# ESB32CARRIER.net
KiCad netlist of a schematic drawn in EAGLE
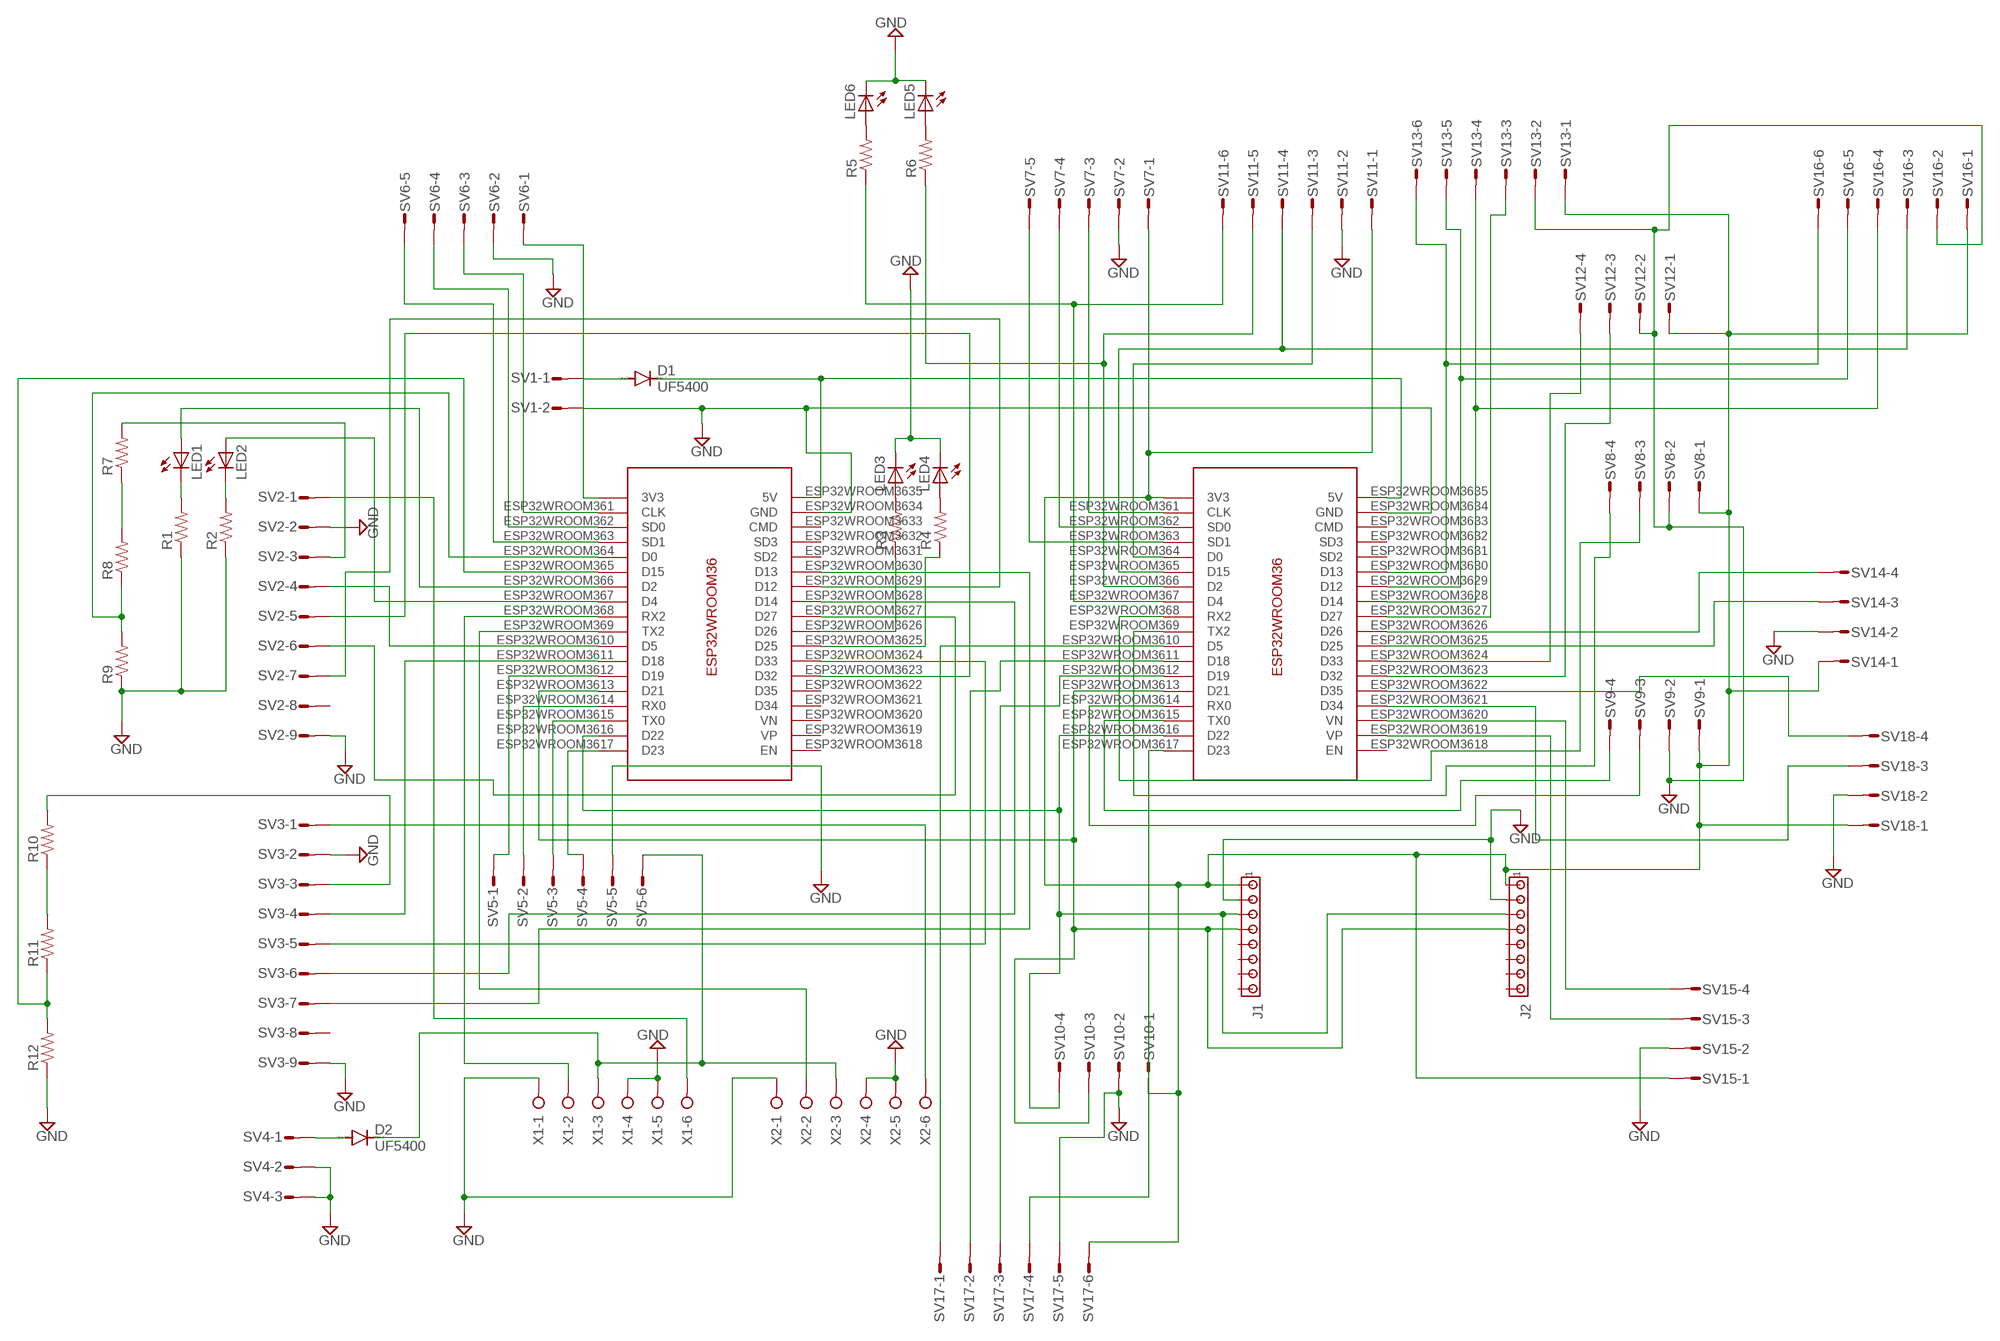
[diagram p0: schematic, sheet 1]

(export (version "E")
  (design (tool "Eeschema 10.0.6"))
  (components
    (comp (ref "D1")
      (value "UF5400")
      (footprint "eagle-import:DO201-15")
      (libsource (lib "eagle-import") (part "UF5400"))
    )
    (comp (ref "D2")
      (value "UF5400")
      (footprint "eagle-import:DO201-15")
      (libsource (lib "eagle-import") (part "UF5400"))
    )
    (comp (ref "J1")
      (value "MTA08-100")
      (footprint "eagle-import:10X08MTA")
      (libsource (lib "eagle-import") (part "MTA08-100"))
    )
    (comp (ref "J2")
      (value "MTA08-100")
      (footprint "eagle-import:10X08MTA")
      (libsource (lib "eagle-import") (part "MTA08-100"))
    )
    (comp (ref "LED1")
      (value "LED3MM")
      (footprint "eagle-import:LED3MM")
      (libsource (lib "eagle-import") (part "LED3MM"))
    )
    (comp (ref "LED2")
      (value "LED3MM")
      (footprint "eagle-import:LED3MM")
      (libsource (lib "eagle-import") (part "LED3MM"))
    )
    (comp (ref "LED3")
      (value "LED3MM")
      (footprint "eagle-import:LED3MM")
      (libsource (lib "eagle-import") (part "LED3MM"))
    )
    (comp (ref "LED4")
      (value "LED3MM")
      (footprint "eagle-import:LED3MM")
      (libsource (lib "eagle-import") (part "LED3MM"))
    )
    (comp (ref "LED5")
      (value "LED3MM")
      (footprint "eagle-import:LED3MM")
      (libsource (lib "eagle-import") (part "LED3MM"))
    )
    (comp (ref "LED6")
      (value "LED3MM")
      (footprint "eagle-import:LED3MM")
      (libsource (lib "eagle-import") (part "LED3MM"))
    )
    (comp (ref "R1")
      (value "R-US_0207/10")
      (footprint "eagle-import:0207_10")
      (libsource (lib "eagle-import") (part "R-US_0207/10"))
    )
    (comp (ref "R2")
      (value "R-US_0207/10")
      (footprint "eagle-import:0207_10")
      (libsource (lib "eagle-import") (part "R-US_0207/10"))
    )
    (comp (ref "R3")
      (value "R-US_0207/10")
      (footprint "eagle-import:0207_10")
      (libsource (lib "eagle-import") (part "R-US_0207/10"))
    )
    (comp (ref "R4")
      (value "R-US_0207/10")
      (footprint "eagle-import:0207_10")
      (libsource (lib "eagle-import") (part "R-US_0207/10"))
    )
    (comp (ref "R5")
      (value "R-US_0207/10")
      (footprint "eagle-import:0207_10")
      (libsource (lib "eagle-import") (part "R-US_0207/10"))
    )
    (comp (ref "R6")
      (value "R-US_0207/10")
      (footprint "eagle-import:0207_10")
      (libsource (lib "eagle-import") (part "R-US_0207/10"))
    )
    (comp (ref "R7")
      (value "R-US_0207/10")
      (footprint "eagle-import:0207_10")
      (libsource (lib "eagle-import") (part "R-US_0207/10"))
    )
    (comp (ref "R8")
      (value "R-US_0207/10")
      (footprint "eagle-import:0207_10")
      (libsource (lib "eagle-import") (part "R-US_0207/10"))
    )
    (comp (ref "R9")
      (value "R-US_0207/10")
      (footprint "eagle-import:0207_10")
      (libsource (lib "eagle-import") (part "R-US_0207/10"))
    )
    (comp (ref "R10")
      (value "R-US_0207/10")
      (footprint "eagle-import:0207_10")
      (libsource (lib "eagle-import") (part "R-US_0207/10"))
    )
    (comp (ref "R11")
      (value "R-US_0207/10")
      (footprint "eagle-import:0207_10")
      (libsource (lib "eagle-import") (part "R-US_0207/10"))
    )
    (comp (ref "R12")
      (value "R-US_0207/10")
      (footprint "eagle-import:0207_10")
      (libsource (lib "eagle-import") (part "R-US_0207/10"))
    )
    (comp (ref "SV1")
      (value "L02P")
      (footprint "eagle-import:L02P")
      (libsource (lib "eagle-import") (part "L02P"))
    )
    (comp (ref "SV2")
      (value "L09P")
      (footprint "eagle-import:L09P")
      (libsource (lib "eagle-import") (part "L09P"))
    )
    (comp (ref "SV3")
      (value "L09P")
      (footprint "eagle-import:L09P")
      (libsource (lib "eagle-import") (part "L09P"))
    )
    (comp (ref "SV4")
      (value "L03P")
      (footprint "eagle-import:L03P")
      (libsource (lib "eagle-import") (part "L03P"))
    )
    (comp (ref "SV5")
      (value "L06P")
      (footprint "eagle-import:L06P")
      (libsource (lib "eagle-import") (part "L06P"))
    )
    (comp (ref "SV6")
      (value "L05P")
      (footprint "eagle-import:L05P")
      (libsource (lib "eagle-import") (part "L05P"))
    )
    (comp (ref "SV7")
      (value "L05P")
      (footprint "eagle-import:L05P")
      (libsource (lib "eagle-import") (part "L05P"))
    )
    (comp (ref "SV8")
      (value "L04P")
      (footprint "eagle-import:L04P")
      (libsource (lib "eagle-import") (part "L04P"))
    )
    (comp (ref "SV9")
      (value "L04P")
      (footprint "eagle-import:L04P")
      (libsource (lib "eagle-import") (part "L04P"))
    )
    (comp (ref "SV10")
      (value "L04P")
      (footprint "eagle-import:L04P")
      (libsource (lib "eagle-import") (part "L04P"))
    )
    (comp (ref "SV11")
      (value "L06P")
      (footprint "eagle-import:L06P")
      (libsource (lib "eagle-import") (part "L06P"))
    )
    (comp (ref "SV12")
      (value "L04P")
      (footprint "eagle-import:L04P")
      (libsource (lib "eagle-import") (part "L04P"))
    )
    (comp (ref "SV13")
      (value "L06P")
      (footprint "eagle-import:L06P")
      (libsource (lib "eagle-import") (part "L06P"))
    )
    (comp (ref "SV14")
      (value "L04P")
      (footprint "eagle-import:L04P")
      (libsource (lib "eagle-import") (part "L04P"))
    )
    (comp (ref "SV15")
      (value "L04P")
      (footprint "eagle-import:L04P")
      (libsource (lib "eagle-import") (part "L04P"))
    )
    (comp (ref "SV16")
      (value "L06P")
      (footprint "eagle-import:L06P")
      (libsource (lib "eagle-import") (part "L06P"))
    )
    (comp (ref "SV17")
      (value "L06P")
      (footprint "eagle-import:L06P")
      (libsource (lib "eagle-import") (part "L06P"))
    )
    (comp (ref "SV18")
      (value "L04P")
      (footprint "eagle-import:L04P")
      (libsource (lib "eagle-import") (part "L04P"))
    )
    (comp (ref "U$1")
      (value "ESP32WROOM36")
      (footprint "eagle-import:ESP32WROOM36PINDIP")
      (libsource (lib "eagle-import") (part "ESP32WROOM36"))
    )
    (comp (ref "U$2")
      (value "ESP32WROOM36")
      (footprint "eagle-import:ESP32WROOM36PINDIP")
      (libsource (lib "eagle-import") (part "ESP32WROOM36"))
    )
    (comp (ref "X1")
      (value "W237-06P")
      (footprint "eagle-import:W237-6P")
      (libsource (lib "eagle-import") (part "W237-06P"))
    )
    (comp (ref "X2")
      (value "W237-06P")
      (footprint "eagle-import:W237-6P")
      (libsource (lib "eagle-import") (part "W237-06P"))
    )
  )
  (nets
    (net (code "1") (name "GND") (class "Default")
      (node (ref "J1") (pin "2") (pinfunction "2_2") (pintype "passive"))
      (node (ref "J2") (pin "2") (pinfunction "2_2") (pintype "passive"))
      (node (ref "LED3") (pin "K") (pinfunction "C_K") (pintype "passive"))
      (node (ref "LED4") (pin "K") (pinfunction "C_K") (pintype "passive"))
      (node (ref "LED5") (pin "K") (pinfunction "C_K") (pintype "passive"))
      (node (ref "LED6") (pin "K") (pinfunction "C_K") (pintype "passive"))
      (node (ref "R1") (pin "1") (pinfunction "1_1") (pintype "passive"))
      (node (ref "R12") (pin "1") (pinfunction "1_1") (pintype "passive"))
      (node (ref "R2") (pin "1") (pinfunction "1_1") (pintype "passive"))
      (node (ref "R9") (pin "1") (pinfunction "1_1") (pintype "passive"))
      (node (ref "SV1") (pin "2") (pinfunction "S_2") (pintype "passive"))
      (node (ref "SV10") (pin "2") (pinfunction "S_2") (pintype "passive"))
      (node (ref "SV11") (pin "2") (pinfunction "S_2") (pintype "passive"))
      (node (ref "SV12") (pin "2") (pinfunction "S_2") (pintype "passive"))
      (node (ref "SV13") (pin "2") (pinfunction "S_2") (pintype "passive"))
      (node (ref "SV14") (pin "2") (pinfunction "S_2") (pintype "passive"))
      (node (ref "SV15") (pin "2") (pinfunction "S_2") (pintype "passive"))
      (node (ref "SV16") (pin "2") (pinfunction "S_2") (pintype "passive"))
      (node (ref "SV17") (pin "5") (pinfunction "S_5") (pintype "passive"))
      (node (ref "SV18") (pin "2") (pinfunction "S_2") (pintype "passive"))
      (node (ref "SV2") (pin "2") (pinfunction "S_2") (pintype "passive"))
      (node (ref "SV2") (pin "9") (pinfunction "S_9") (pintype "passive"))
      (node (ref "SV3") (pin "2") (pinfunction "S_2") (pintype "passive"))
      (node (ref "SV3") (pin "9") (pinfunction "S_9") (pintype "passive"))
      (node (ref "SV4") (pin "2") (pinfunction "S_2") (pintype "passive"))
      (node (ref "SV4") (pin "3") (pinfunction "S_3") (pintype "passive"))
      (node (ref "SV5") (pin "5") (pinfunction "S_5") (pintype "passive"))
      (node (ref "SV6") (pin "2") (pinfunction "S_2") (pintype "passive"))
      (node (ref "SV7") (pin "2") (pinfunction "S_2") (pintype "passive"))
      (node (ref "SV8") (pin "2") (pinfunction "S_2") (pintype "passive"))
      (node (ref "SV9") (pin "2") (pinfunction "S_2") (pintype "passive"))
      (node (ref "U$1") (pin "ESP32WROOM3634") (pinfunction "GND_ESP32WROOM3634") (pintype "bidirectional"))
      (node (ref "U$2") (pin "ESP32WROOM3634") (pinfunction "GND_ESP32WROOM3634") (pintype "bidirectional"))
      (node (ref "X1") (pin "1") (pinfunction "KL_1") (pintype "passive"))
      (node (ref "X1") (pin "4") (pinfunction "KL_4") (pintype "passive"))
      (node (ref "X1") (pin "5") (pinfunction "KL_5") (pintype "passive"))
      (node (ref "X2") (pin "1") (pinfunction "KL_1") (pintype "passive"))
      (node (ref "X2") (pin "4") (pinfunction "KL_4") (pintype "passive"))
      (node (ref "X2") (pin "5") (pinfunction "KL_5") (pintype "passive"))
    )
    (net (code "2") (name "Net-(LED1-C)") (class "Default")
      (node (ref "LED1") (pin "K") (pinfunction "C_K") (pintype "passive"))
      (node (ref "R1") (pin "2") (pinfunction "2_2") (pintype "passive"))
    )
    (net (code "3") (name "Net-(LED2-C)") (class "Default")
      (node (ref "LED2") (pin "K") (pinfunction "C_K") (pintype "passive"))
      (node (ref "R2") (pin "2") (pinfunction "2_2") (pintype "passive"))
    )
    (net (code "4") (name "Net-(LED3-PadA)") (class "Default")
      (node (ref "LED3") (pin "A") (pinfunction "A_A") (pintype "passive"))
      (node (ref "R3") (pin "2") (pinfunction "2_2") (pintype "passive"))
    )
    (net (code "5") (name "Net-(LED4-PadA)") (class "Default")
      (node (ref "LED4") (pin "A") (pinfunction "A_A") (pintype "passive"))
      (node (ref "R4") (pin "2") (pinfunction "2_2") (pintype "passive"))
    )
    (net (code "6") (name "Net-(LED5-PadA)") (class "Default")
      (node (ref "LED5") (pin "A") (pinfunction "A_A") (pintype "passive"))
      (node (ref "R6") (pin "2") (pinfunction "2_2") (pintype "passive"))
    )
    (net (code "7") (name "Net-(LED6-PadA)") (class "Default")
      (node (ref "LED6") (pin "A") (pinfunction "A_A") (pintype "passive"))
      (node (ref "R5") (pin "2") (pinfunction "2_2") (pintype "passive"))
    )
    (net (code "8") (name "Net-(R7-Pad1)") (class "Default")
      (node (ref "R7") (pin "1") (pinfunction "1_1") (pintype "passive"))
      (node (ref "R8") (pin "2") (pinfunction "2_2") (pintype "passive"))
    )
    (net (code "9") (name "Net-(R10-Pad1)") (class "Default")
      (node (ref "R10") (pin "1") (pinfunction "1_1") (pintype "passive"))
      (node (ref "R11") (pin "2") (pinfunction "2_2") (pintype "passive"))
    )
    (net (code "10") (name "Net-(SV1A-S)") (class "Default")
      (node (ref "D1") (pin "A") (pinfunction "A_A") (pintype "passive"))
      (node (ref "SV1") (pin "1") (pinfunction "S_1") (pintype "passive"))
    )
    (net (code "11") (name "Net-(SV2A-S)") (class "Default")
      (node (ref "SV2") (pin "1") (pinfunction "S_1") (pintype "passive"))
      (node (ref "X1") (pin "6") (pinfunction "KL_6") (pintype "passive"))
    )
    (net (code "12") (name "Net-(SV2C-S)") (class "Default")
      (node (ref "R7") (pin "2") (pinfunction "2_2") (pintype "passive"))
      (node (ref "SV2") (pin "3") (pinfunction "S_3") (pintype "passive"))
    )
    (net (code "13") (name "Net-(SV2D-S)") (class "Default")
      (node (ref "SV2") (pin "4") (pinfunction "S_4") (pintype "passive"))
      (node (ref "U$1") (pin "ESP32WROOM3610") (pinfunction "D5_ESP32WROOM3610") (pintype "bidirectional"))
    )
    (net (code "14") (name "Net-(SV2E-S)") (class "Default")
      (node (ref "SV2") (pin "5") (pinfunction "S_5") (pintype "passive"))
      (node (ref "U$1") (pin "ESP32WROOM3623") (pinfunction "D32_ESP32WROOM3623") (pintype "bidirectional"))
    )
    (net (code "15") (name "Net-(SV2F-S)") (class "Default")
      (node (ref "SV2") (pin "6") (pinfunction "S_6") (pintype "passive"))
      (node (ref "U$1") (pin "ESP32WROOM3627") (pinfunction "D27_ESP32WROOM3627") (pintype "bidirectional"))
    )
    (net (code "16") (name "Net-(SV2G-S)") (class "Default")
      (node (ref "SV2") (pin "7") (pinfunction "S_7") (pintype "passive"))
      (node (ref "U$1") (pin "ESP32WROOM3629") (pinfunction "D12_ESP32WROOM3629") (pintype "bidirectional"))
    )
    (net (code "17") (name "Net-(SV3A-S)") (class "Default")
      (node (ref "SV3") (pin "1") (pinfunction "S_1") (pintype "passive"))
      (node (ref "X2") (pin "6") (pinfunction "KL_6") (pintype "passive"))
    )
    (net (code "18") (name "Net-(SV3C-S)") (class "Default")
      (node (ref "R10") (pin "2") (pinfunction "2_2") (pintype "passive"))
      (node (ref "SV3") (pin "3") (pinfunction "S_3") (pintype "passive"))
    )
    (net (code "19") (name "Net-(SV3D-S)") (class "Default")
      (node (ref "SV3") (pin "4") (pinfunction "S_4") (pintype "passive"))
      (node (ref "U$1") (pin "ESP32WROOM3611") (pinfunction "D18_ESP32WROOM3611") (pintype "bidirectional"))
    )
    (net (code "20") (name "Net-(SV3E-S)") (class "Default")
      (node (ref "SV3") (pin "5") (pinfunction "S_5") (pintype "passive"))
      (node (ref "U$1") (pin "ESP32WROOM3624") (pinfunction "D33_ESP32WROOM3624") (pintype "bidirectional"))
    )
    (net (code "21") (name "Net-(SV3F-S)") (class "Default")
      (node (ref "SV3") (pin "6") (pinfunction "S_6") (pintype "passive"))
      (node (ref "U$1") (pin "ESP32WROOM3628") (pinfunction "D14_ESP32WROOM3628") (pintype "bidirectional"))
    )
    (net (code "22") (name "Net-(SV3G-S)") (class "Default")
      (node (ref "SV3") (pin "7") (pinfunction "S_7") (pintype "passive"))
      (node (ref "U$1") (pin "ESP32WROOM3630") (pinfunction "D13_ESP32WROOM3630") (pintype "bidirectional"))
    )
    (net (code "23") (name "Net-(SV4A-S)") (class "Default")
      (node (ref "D2") (pin "A") (pinfunction "A_A") (pintype "passive"))
      (node (ref "SV4") (pin "1") (pinfunction "S_1") (pintype "passive"))
    )
    (net (code "24") (name "Net-(SV5A-S)") (class "Default")
      (node (ref "SV5") (pin "1") (pinfunction "S_1") (pintype "passive"))
      (node (ref "U$1") (pin "ESP32WROOM3612") (pinfunction "D19_ESP32WROOM3612") (pintype "bidirectional"))
    )
    (net (code "25") (name "Net-(SV5B-S)") (class "Default")
      (node (ref "SV5") (pin "2") (pinfunction "S_2") (pintype "passive"))
      (node (ref "U$1") (pin "ESP32WROOM3614") (pinfunction "RX0_ESP32WROOM3614") (pintype "bidirectional"))
    )
    (net (code "26") (name "Net-(SV5C-S)") (class "Default")
      (node (ref "SV5") (pin "3") (pinfunction "S_3") (pintype "passive"))
      (node (ref "U$1") (pin "ESP32WROOM3615") (pinfunction "TX0_ESP32WROOM3615") (pintype "bidirectional"))
    )
    (net (code "27") (name "Net-(SV5D-S)") (class "Default")
      (node (ref "SV5") (pin "4") (pinfunction "S_4") (pintype "passive"))
      (node (ref "U$1") (pin "ESP32WROOM3617") (pinfunction "D23_ESP32WROOM3617") (pintype "bidirectional"))
    )
    (net (code "28") (name "Net-(SV5F-S)") (class "Default")
      (node (ref "D2") (pin "C") (pinfunction "C_C") (pintype "passive"))
      (node (ref "SV5") (pin "6") (pinfunction "S_6") (pintype "passive"))
      (node (ref "X1") (pin "3") (pinfunction "KL_3") (pintype "passive"))
      (node (ref "X2") (pin "3") (pinfunction "KL_3") (pintype "passive"))
    )
    (net (code "29") (name "Net-(SV6A-S)") (class "Default")
      (node (ref "SV6") (pin "1") (pinfunction "S_1") (pintype "passive"))
      (node (ref "U$1") (pin "ESP32WROOM360") (pinfunction "3V3_ESP32WROOM360") (pintype "bidirectional"))
    )
    (net (code "30") (name "Net-(SV6C-S)") (class "Default")
      (node (ref "SV6") (pin "3") (pinfunction "S_3") (pintype "passive"))
      (node (ref "U$1") (pin "ESP32WROOM361") (pinfunction "CLK_ESP32WROOM361") (pintype "bidirectional"))
    )
    (net (code "31") (name "Net-(SV6D-S)") (class "Default")
      (node (ref "SV6") (pin "4") (pinfunction "S_4") (pintype "passive"))
      (node (ref "U$1") (pin "ESP32WROOM362") (pinfunction "SD0_ESP32WROOM362") (pintype "bidirectional"))
    )
    (net (code "32") (name "Net-(SV6E-S)") (class "Default")
      (node (ref "SV6") (pin "5") (pinfunction "S_5") (pintype "passive"))
      (node (ref "U$1") (pin "ESP32WROOM363") (pinfunction "SD1_ESP32WROOM363") (pintype "bidirectional"))
    )
    (net (code "33") (name "Net-(SV7C-S)") (class "Default")
      (node (ref "SV7") (pin "3") (pinfunction "S_3") (pintype "passive"))
      (node (ref "U$2") (pin "ESP32WROOM361") (pinfunction "CLK_ESP32WROOM361") (pintype "bidirectional"))
    )
    (net (code "34") (name "Net-(SV7D-S)") (class "Default")
      (node (ref "SV7") (pin "4") (pinfunction "S_4") (pintype "passive"))
      (node (ref "U$2") (pin "ESP32WROOM362") (pinfunction "SD0_ESP32WROOM362") (pintype "bidirectional"))
    )
    (net (code "35") (name "Net-(SV7E-S)") (class "Default")
      (node (ref "SV7") (pin "5") (pinfunction "S_5") (pintype "passive"))
      (node (ref "U$2") (pin "ESP32WROOM363") (pinfunction "SD1_ESP32WROOM363") (pintype "bidirectional"))
    )
    (net (code "36") (name "Net-(SV8C-S)") (class "Default")
      (node (ref "SV8") (pin "3") (pinfunction "S_3") (pintype "passive"))
      (node (ref "U$2") (pin "ESP32WROOM368") (pinfunction "RX2_ESP32WROOM368") (pintype "bidirectional"))
    )
    (net (code "37") (name "Net-(SV8D-S)") (class "Default")
      (node (ref "SV8") (pin "4") (pinfunction "S_4") (pintype "passive"))
      (node (ref "U$2") (pin "ESP32WROOM369") (pinfunction "TX2_ESP32WROOM369") (pintype "bidirectional"))
    )
    (net (code "38") (name "Net-(SV9C-S)") (class "Default")
      (node (ref "SV9") (pin "3") (pinfunction "S_3") (pintype "passive"))
      (node (ref "U$2") (pin "ESP32WROOM3614") (pinfunction "RX0_ESP32WROOM3614") (pintype "bidirectional"))
    )
    (net (code "39") (name "Net-(SV9D-S)") (class "Default")
      (node (ref "SV9") (pin "4") (pinfunction "S_4") (pintype "passive"))
      (node (ref "U$2") (pin "ESP32WROOM3615") (pinfunction "TX0_ESP32WROOM3615") (pintype "bidirectional"))
    )
    (net (code "40") (name "Net-(SV10A-S)") (class "Default")
      (node (ref "J1") (pin "1") (pinfunction "1_1") (pintype "passive"))
      (node (ref "J2") (pin "1") (pinfunction "1_1") (pintype "passive"))
      (node (ref "SV10") (pin "1") (pinfunction "S_1") (pintype "passive"))
      (node (ref "SV11") (pin "1") (pinfunction "S_1") (pintype "passive"))
      (node (ref "SV12") (pin "1") (pinfunction "S_1") (pintype "passive"))
      (node (ref "SV13") (pin "1") (pinfunction "S_1") (pintype "passive"))
      (node (ref "SV14") (pin "1") (pinfunction "S_1") (pintype "passive"))
      (node (ref "SV15") (pin "1") (pinfunction "S_1") (pintype "passive"))
      (node (ref "SV16") (pin "1") (pinfunction "S_1") (pintype "passive"))
      (node (ref "SV17") (pin "6") (pinfunction "S_6") (pintype "passive"))
      (node (ref "SV18") (pin "1") (pinfunction "S_1") (pintype "passive"))
      (node (ref "SV7") (pin "1") (pinfunction "S_1") (pintype "passive"))
      (node (ref "SV8") (pin "1") (pinfunction "S_1") (pintype "passive"))
      (node (ref "SV9") (pin "1") (pinfunction "S_1") (pintype "passive"))
      (node (ref "U$2") (pin "ESP32WROOM360") (pinfunction "3V3_ESP32WROOM360") (pintype "bidirectional"))
    )
    (net (code "41") (name "Net-(SV10C-S)") (class "Default")
      (node (ref "J1") (pin "4") (pinfunction "4_4") (pintype "passive"))
      (node (ref "J2") (pin "4") (pinfunction "4_4") (pintype "passive"))
      (node (ref "SV10") (pin "3") (pinfunction "S_3") (pintype "passive"))
      (node (ref "U$1") (pin "ESP32WROOM3613") (pinfunction "D21_ESP32WROOM3613") (pintype "bidirectional"))
      (node (ref "U$2") (pin "ESP32WROOM3613") (pinfunction "D21_ESP32WROOM3613") (pintype "bidirectional"))
    )
    (net (code "42") (name "Net-(SV10D-S)") (class "Default")
      (node (ref "J1") (pin "3") (pinfunction "3_3") (pintype "passive"))
      (node (ref "J2") (pin "3") (pinfunction "3_3") (pintype "passive"))
      (node (ref "SV10") (pin "4") (pinfunction "S_4") (pintype "passive"))
      (node (ref "U$1") (pin "ESP32WROOM3616") (pinfunction "D22_ESP32WROOM3616") (pintype "bidirectional"))
      (node (ref "U$2") (pin "ESP32WROOM3616") (pinfunction "D22_ESP32WROOM3616") (pintype "bidirectional"))
    )
    (net (code "43") (name "Net-(SV11C-S)") (class "Default")
      (node (ref "SV11") (pin "3") (pinfunction "S_3") (pintype "passive"))
      (node (ref "U$2") (pin "ESP32WROOM364") (pinfunction "D0_ESP32WROOM364") (pintype "bidirectional"))
    )
    (net (code "44") (name "Net-(SV11D-S)") (class "Default")
      (node (ref "SV11") (pin "4") (pinfunction "S_4") (pintype "passive"))
      (node (ref "SV16") (pin "3") (pinfunction "S_3") (pintype "passive"))
      (node (ref "U$2") (pin "ESP32WROOM365") (pinfunction "D15_ESP32WROOM365") (pintype "bidirectional"))
    )
    (net (code "45") (name "Net-(SV11E-S)") (class "Default")
      (node (ref "R6") (pin "1") (pinfunction "1_1") (pintype "passive"))
      (node (ref "SV11") (pin "5") (pinfunction "S_5") (pintype "passive"))
      (node (ref "U$2") (pin "ESP32WROOM366") (pinfunction "D2_ESP32WROOM366") (pintype "bidirectional"))
    )
    (net (code "46") (name "Net-(SV11F-S)") (class "Default")
      (node (ref "R5") (pin "1") (pinfunction "1_1") (pintype "passive"))
      (node (ref "SV11") (pin "6") (pinfunction "S_6") (pintype "passive"))
      (node (ref "U$2") (pin "ESP32WROOM367") (pinfunction "D4_ESP32WROOM367") (pintype "bidirectional"))
    )
    (net (code "47") (name "Net-(SV12C-S)") (class "Default")
      (node (ref "SV12") (pin "3") (pinfunction "S_3") (pintype "passive"))
      (node (ref "U$2") (pin "ESP32WROOM3623") (pinfunction "D32_ESP32WROOM3623") (pintype "bidirectional"))
    )
    (net (code "48") (name "Net-(SV12D-S)") (class "Default")
      (node (ref "SV12") (pin "4") (pinfunction "S_4") (pintype "passive"))
      (node (ref "U$2") (pin "ESP32WROOM3624") (pinfunction "D33_ESP32WROOM3624") (pintype "bidirectional"))
    )
    (net (code "49") (name "Net-(SV13C-S)") (class "Default")
      (node (ref "SV13") (pin "3") (pinfunction "S_3") (pintype "passive"))
      (node (ref "U$2") (pin "ESP32WROOM3627") (pinfunction "D27_ESP32WROOM3627") (pintype "bidirectional"))
    )
    (net (code "50") (name "Net-(SV13D-S)") (class "Default")
      (node (ref "SV13") (pin "4") (pinfunction "S_4") (pintype "passive"))
      (node (ref "SV16") (pin "4") (pinfunction "S_4") (pintype "passive"))
      (node (ref "U$2") (pin "ESP32WROOM3628") (pinfunction "D14_ESP32WROOM3628") (pintype "bidirectional"))
    )
    (net (code "51") (name "Net-(SV13E-S)") (class "Default")
      (node (ref "SV13") (pin "5") (pinfunction "S_5") (pintype "passive"))
      (node (ref "SV16") (pin "5") (pinfunction "S_5") (pintype "passive"))
      (node (ref "U$2") (pin "ESP32WROOM3629") (pinfunction "D12_ESP32WROOM3629") (pintype "bidirectional"))
    )
    (net (code "52") (name "Net-(SV13F-S)") (class "Default")
      (node (ref "SV13") (pin "6") (pinfunction "S_6") (pintype "passive"))
      (node (ref "SV16") (pin "6") (pinfunction "S_6") (pintype "passive"))
      (node (ref "U$2") (pin "ESP32WROOM3630") (pinfunction "D13_ESP32WROOM3630") (pintype "bidirectional"))
    )
    (net (code "53") (name "Net-(SV14C-S)") (class "Default")
      (node (ref "SV14") (pin "3") (pinfunction "S_3") (pintype "passive"))
      (node (ref "U$2") (pin "ESP32WROOM3625") (pinfunction "D25_ESP32WROOM3625") (pintype "bidirectional"))
    )
    (net (code "54") (name "Net-(SV14D-S)") (class "Default")
      (node (ref "SV14") (pin "4") (pinfunction "S_4") (pintype "passive"))
      (node (ref "U$2") (pin "ESP32WROOM3626") (pinfunction "D26_ESP32WROOM3626") (pintype "bidirectional"))
    )
    (net (code "55") (name "Net-(SV15C-S)") (class "Default")
      (node (ref "SV15") (pin "3") (pinfunction "S_3") (pintype "passive"))
      (node (ref "U$2") (pin "ESP32WROOM3619") (pinfunction "VP_ESP32WROOM3619") (pintype "bidirectional"))
    )
    (net (code "56") (name "Net-(SV15D-S)") (class "Default")
      (node (ref "SV15") (pin "4") (pinfunction "S_4") (pintype "passive"))
      (node (ref "U$2") (pin "ESP32WROOM3620") (pinfunction "VN_ESP32WROOM3620") (pintype "bidirectional"))
    )
    (net (code "57") (name "Net-(SV17A-S)") (class "Default")
      (node (ref "SV17") (pin "1") (pinfunction "S_1") (pintype "passive"))
      (node (ref "U$2") (pin "ESP32WROOM3610") (pinfunction "D5_ESP32WROOM3610") (pintype "bidirectional"))
    )
    (net (code "58") (name "Net-(SV17B-S)") (class "Default")
      (node (ref "SV17") (pin "2") (pinfunction "S_2") (pintype "passive"))
      (node (ref "U$2") (pin "ESP32WROOM3611") (pinfunction "D18_ESP32WROOM3611") (pintype "bidirectional"))
    )
    (net (code "59") (name "Net-(SV17C-S)") (class "Default")
      (node (ref "SV17") (pin "3") (pinfunction "S_3") (pintype "passive"))
      (node (ref "U$2") (pin "ESP32WROOM3612") (pinfunction "D19_ESP32WROOM3612") (pintype "bidirectional"))
    )
    (net (code "60") (name "Net-(SV17D-S)") (class "Default")
      (node (ref "SV17") (pin "4") (pinfunction "S_4") (pintype "passive"))
      (node (ref "U$2") (pin "ESP32WROOM3617") (pinfunction "D23_ESP32WROOM3617") (pintype "bidirectional"))
    )
    (net (code "61") (name "Net-(SV18C-S)") (class "Default")
      (node (ref "SV18") (pin "3") (pinfunction "S_3") (pintype "passive"))
      (node (ref "U$2") (pin "ESP32WROOM3621") (pinfunction "D34_ESP32WROOM3621") (pintype "bidirectional"))
    )
    (net (code "62") (name "Net-(SV18D-S)") (class "Default")
      (node (ref "SV18") (pin "4") (pinfunction "S_4") (pintype "passive"))
      (node (ref "U$2") (pin "ESP32WROOM3622") (pinfunction "D35_ESP32WROOM3622") (pintype "bidirectional"))
    )
    (net (code "63") (name "Net-(U$1-5V)") (class "Default")
      (node (ref "D1") (pin "C") (pinfunction "C_C") (pintype "passive"))
      (node (ref "U$1") (pin "ESP32WROOM3635") (pinfunction "5V_ESP32WROOM3635") (pintype "bidirectional"))
      (node (ref "U$2") (pin "ESP32WROOM3635") (pinfunction "5V_ESP32WROOM3635") (pintype "bidirectional"))
    )
    (net (code "64") (name "Net-(U$1-D0)") (class "Default")
      (node (ref "R8") (pin "1") (pinfunction "1_1") (pintype "passive"))
      (node (ref "R9") (pin "2") (pinfunction "2_2") (pintype "passive"))
      (node (ref "U$1") (pin "ESP32WROOM364") (pinfunction "D0_ESP32WROOM364") (pintype "bidirectional"))
    )
    (net (code "65") (name "Net-(U$1-D2)") (class "Default")
      (node (ref "LED1") (pin "A") (pinfunction "A_A") (pintype "passive"))
      (node (ref "U$1") (pin "ESP32WROOM366") (pinfunction "D2_ESP32WROOM366") (pintype "bidirectional"))
    )
    (net (code "66") (name "Net-(U$1-D4)") (class "Default")
      (node (ref "LED2") (pin "A") (pinfunction "A_A") (pintype "passive"))
      (node (ref "U$1") (pin "ESP32WROOM367") (pinfunction "D4_ESP32WROOM367") (pintype "bidirectional"))
    )
    (net (code "67") (name "Net-(U$1-D15)") (class "Default")
      (node (ref "R11") (pin "1") (pinfunction "1_1") (pintype "passive"))
      (node (ref "R12") (pin "2") (pinfunction "2_2") (pintype "passive"))
      (node (ref "U$1") (pin "ESP32WROOM365") (pinfunction "D15_ESP32WROOM365") (pintype "bidirectional"))
    )
    (net (code "68") (name "Net-(U$1-D25)") (class "Default")
      (node (ref "R4") (pin "1") (pinfunction "1_1") (pintype "passive"))
      (node (ref "U$1") (pin "ESP32WROOM3625") (pinfunction "D25_ESP32WROOM3625") (pintype "bidirectional"))
    )
    (net (code "69") (name "Net-(U$1-D26)") (class "Default")
      (node (ref "R3") (pin "1") (pinfunction "1_1") (pintype "passive"))
      (node (ref "U$1") (pin "ESP32WROOM3626") (pinfunction "D26_ESP32WROOM3626") (pintype "bidirectional"))
    )
    (net (code "70") (name "Net-(U$1-RX2)") (class "Default")
      (node (ref "U$1") (pin "ESP32WROOM368") (pinfunction "RX2_ESP32WROOM368") (pintype "bidirectional"))
      (node (ref "X1") (pin "2") (pinfunction "KL_2") (pintype "passive"))
    )
    (net (code "71") (name "Net-(U$1-TX2)") (class "Default")
      (node (ref "U$1") (pin "ESP32WROOM369") (pinfunction "TX2_ESP32WROOM369") (pintype "bidirectional"))
      (node (ref "X2") (pin "2") (pinfunction "KL_2") (pintype "passive"))
    )
    (net (code "72") (name "unconnected-(J1-Pad5)") (class "Default")
      (node (ref "J1") (pin "5") (pinfunction "5_5") (pintype "passive"))
    )
    (net (code "73") (name "unconnected-(J1-Pad6)") (class "Default")
      (node (ref "J1") (pin "6") (pinfunction "6_6") (pintype "passive"))
    )
    (net (code "74") (name "unconnected-(J1-Pad7)") (class "Default")
      (node (ref "J1") (pin "7") (pinfunction "7_7") (pintype "passive"))
    )
    (net (code "75") (name "unconnected-(J1-Pad8)") (class "Default")
      (node (ref "J1") (pin "8") (pinfunction "8_8") (pintype "passive"))
    )
    (net (code "76") (name "unconnected-(J2-Pad5)") (class "Default")
      (node (ref "J2") (pin "5") (pinfunction "5_5") (pintype "passive"))
    )
    (net (code "77") (name "unconnected-(J2-Pad6)") (class "Default")
      (node (ref "J2") (pin "6") (pinfunction "6_6") (pintype "passive"))
    )
    (net (code "78") (name "unconnected-(J2-Pad7)") (class "Default")
      (node (ref "J2") (pin "7") (pinfunction "7_7") (pintype "passive"))
    )
    (net (code "79") (name "unconnected-(J2-Pad8)") (class "Default")
      (node (ref "J2") (pin "8") (pinfunction "8_8") (pintype "passive"))
    )
    (net (code "80") (name "unconnected-(SV2H-S-Pad8)") (class "Default")
      (node (ref "SV2") (pin "8") (pinfunction "S_8") (pintype "passive"))
    )
    (net (code "81") (name "unconnected-(SV3H-S-Pad8)") (class "Default")
      (node (ref "SV3") (pin "8") (pinfunction "S_8") (pintype "passive"))
    )
    (net (code "82") (name "unconnected-(U$1-CMD-PadESP32WROOM3633)") (class "Default")
      (node (ref "U$1") (pin "ESP32WROOM3633") (pinfunction "CMD_ESP32WROOM3633") (pintype "bidirectional"))
    )
    (net (code "83") (name "unconnected-(U$1-D34-PadESP32WROOM3621)") (class "Default")
      (node (ref "U$1") (pin "ESP32WROOM3621") (pinfunction "D34_ESP32WROOM3621") (pintype "bidirectional"))
    )
    (net (code "84") (name "unconnected-(U$1-D35-PadESP32WROOM3622)") (class "Default")
      (node (ref "U$1") (pin "ESP32WROOM3622") (pinfunction "D35_ESP32WROOM3622") (pintype "bidirectional"))
    )
    (net (code "85") (name "unconnected-(U$1-EN-PadESP32WROOM3618)") (class "Default")
      (node (ref "U$1") (pin "ESP32WROOM3618") (pinfunction "EN_ESP32WROOM3618") (pintype "bidirectional"))
    )
    (net (code "86") (name "unconnected-(U$1-SD2-PadESP32WROOM3631)") (class "Default")
      (node (ref "U$1") (pin "ESP32WROOM3631") (pinfunction "SD2_ESP32WROOM3631") (pintype "bidirectional"))
    )
    (net (code "87") (name "unconnected-(U$1-SD3-PadESP32WROOM3632)") (class "Default")
      (node (ref "U$1") (pin "ESP32WROOM3632") (pinfunction "SD3_ESP32WROOM3632") (pintype "bidirectional"))
    )
    (net (code "88") (name "unconnected-(U$1-VN-PadESP32WROOM3620)") (class "Default")
      (node (ref "U$1") (pin "ESP32WROOM3620") (pinfunction "VN_ESP32WROOM3620") (pintype "bidirectional"))
    )
    (net (code "89") (name "unconnected-(U$1-VP-PadESP32WROOM3619)") (class "Default")
      (node (ref "U$1") (pin "ESP32WROOM3619") (pinfunction "VP_ESP32WROOM3619") (pintype "bidirectional"))
    )
    (net (code "90") (name "unconnected-(U$2-CMD-PadESP32WROOM3633)") (class "Default")
      (node (ref "U$2") (pin "ESP32WROOM3633") (pinfunction "CMD_ESP32WROOM3633") (pintype "bidirectional"))
    )
    (net (code "91") (name "unconnected-(U$2-EN-PadESP32WROOM3618)") (class "Default")
      (node (ref "U$2") (pin "ESP32WROOM3618") (pinfunction "EN_ESP32WROOM3618") (pintype "bidirectional"))
    )
    (net (code "92") (name "unconnected-(U$2-SD2-PadESP32WROOM3631)") (class "Default")
      (node (ref "U$2") (pin "ESP32WROOM3631") (pinfunction "SD2_ESP32WROOM3631") (pintype "bidirectional"))
    )
    (net (code "93") (name "unconnected-(U$2-SD3-PadESP32WROOM3632)") (class "Default")
      (node (ref "U$2") (pin "ESP32WROOM3632") (pinfunction "SD3_ESP32WROOM3632") (pintype "bidirectional"))
    )
  )
)
